# Sheet2.net
KiCad netlist of a schematic drawn in Altium Designer
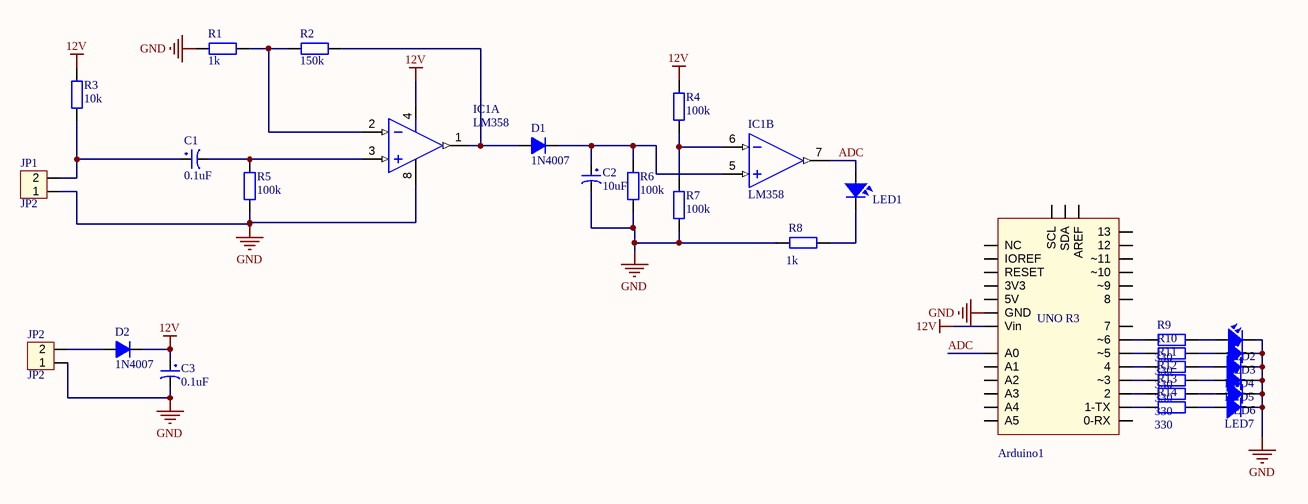
[diagram p0: Sheet2.SchDoc]

(export (version "E")
  (design (tool "Eeschema 10.0.6"))
  (components
    (comp (ref "Arduino1")
      (value "Arduino Uno R3")
      (footprint "Arduino UNO R3")
      (description "Arduino UNO R3")
      (libsource (lib "LIBRARY") (part "Arduino Uno R3"))
    )
    (comp (ref "C1")
      (value "0.1uF")
      (footprint "CP1/2")
      (description "Cap P  0,1uF < 22uF , 16 - 50V")
      (libsource (lib "") (part "CP1_1"))
    )
    (comp (ref "C2")
      (value "10uF")
      (footprint "CP1/2")
      (description "Cap P  0,1uF < 22uF , 16 - 50V")
      (libsource (lib "syhaunguyen") (part "CP1"))
    )
    (comp (ref "C3")
      (value "0.1uF")
      (footprint "CP1/2")
      (description "Cap P  0,1uF < 22uF , 16 - 50V")
      (libsource (lib "syhaunguyen") (part "CP1"))
    )
    (comp (ref "D1")
      (value "1N4007")
      (footprint "D1A")
      (description "Diode 1A")
      (libsource (lib "syhaunguyen") (part "D1A"))
    )
    (comp (ref "D2")
      (value "1N4007")
      (footprint "D1A")
      (description "Diode 1A")
      (libsource (lib "syhaunguyen") (part "D1A"))
    )
    (comp (ref "IC1")
      (value "LM358")
      (footprint "DIP8")
      (description "Low-Power Dual Operational Amplifier")
      (libsource (lib "LIBRARY") (part "LM358"))
    )
    (comp (ref "JP1")
      (value "JP2")
      (footprint "CON2")
      (description "Connector 2")
      (libsource (lib "syhaunguyen") (part "Con2"))
    )
    (comp (ref "JP2")
      (value "JP2")
      (footprint "CON2")
      (description "Connector 2")
      (libsource (lib "syhaunguyen") (part "Con2"))
    )
    (comp (ref "LED1")
      (value "LED")
      (footprint "LED-3")
      (description "LED Single colour Green and Red")
      (libsource (lib "syhaunguyen") (part "LED"))
    )
    (comp (ref "LED2")
      (value "LED")
      (footprint "LED-3")
      (description "LED Single colour Green and Red")
      (libsource (lib "syhaunguyen") (part "LED"))
    )
    (comp (ref "LED3")
      (value "LED")
      (footprint "LED-3")
      (description "LED Single colour Green and Red")
      (libsource (lib "syhaunguyen") (part "LED"))
    )
    (comp (ref "LED4")
      (value "LED")
      (footprint "LED-3")
      (description "LED Single colour Green and Red")
      (libsource (lib "syhaunguyen") (part "LED"))
    )
    (comp (ref "LED5")
      (value "LED")
      (footprint "LED-3")
      (description "LED Single colour Green and Red")
      (libsource (lib "syhaunguyen") (part "LED"))
    )
    (comp (ref "LED6")
      (value "LED")
      (footprint "LED-3")
      (description "LED Single colour Green and Red")
      (libsource (lib "syhaunguyen") (part "LED"))
    )
    (comp (ref "LED7")
      (value "LED")
      (footprint "LED-3")
      (description "LED Single colour Green and Red")
      (libsource (lib "syhaunguyen") (part "LED"))
    )
    (comp (ref "R1")
      (value "1k")
      (footprint "R1/4W")
      (description "Resistor 1/4W")
      (libsource (lib "syhaunguyen") (part "R1/4W"))
    )
    (comp (ref "R2")
      (value "150k")
      (footprint "R1/4W")
      (description "Resistor 1/4W")
      (libsource (lib "syhaunguyen") (part "R1/4W"))
    )
    (comp (ref "R3")
      (value "10k")
      (footprint "R1/4W")
      (description "Resistor 1/4W")
      (libsource (lib "syhaunguyen") (part "R1/4W"))
    )
    (comp (ref "R4")
      (value "100k")
      (footprint "R1/4W")
      (description "Resistor 1/4W")
      (libsource (lib "syhaunguyen") (part "R1/4W"))
    )
    (comp (ref "R5")
      (value "100k")
      (footprint "R1/4W")
      (description "Resistor 1/4W")
      (libsource (lib "syhaunguyen") (part "R1/4W"))
    )
    (comp (ref "R6")
      (value "100k")
      (footprint "R1/4W")
      (description "Resistor 1/4W")
      (libsource (lib "syhaunguyen") (part "R1/4W"))
    )
    (comp (ref "R7")
      (value "100k")
      (footprint "R1/4W")
      (description "Resistor 1/4W")
      (libsource (lib "syhaunguyen") (part "R1/4W"))
    )
    (comp (ref "R8")
      (value "1k")
      (footprint "R1/4W")
      (description "Resistor 1/4W")
      (libsource (lib "syhaunguyen") (part "R1/4W"))
    )
    (comp (ref "R9")
      (value "330")
      (footprint "R1/4W")
      (description "Resistor 1/4W")
      (libsource (lib "syhaunguyen") (part "R1/4W"))
    )
    (comp (ref "R10")
      (value "330")
      (footprint "R1/4W")
      (description "Resistor 1/4W")
      (libsource (lib "syhaunguyen") (part "R1/4W"))
    )
    (comp (ref "R11")
      (value "330")
      (footprint "R1/4W")
      (description "Resistor 1/4W")
      (libsource (lib "syhaunguyen") (part "R1/4W"))
    )
    (comp (ref "R12")
      (value "330")
      (footprint "R1/4W")
      (description "Resistor 1/4W")
      (libsource (lib "syhaunguyen") (part "R1/4W"))
    )
    (comp (ref "R13")
      (value "330")
      (footprint "R1/4W")
      (description "Resistor 1/4W")
      (libsource (lib "syhaunguyen") (part "R1/4W"))
    )
    (comp (ref "R14")
      (value "330")
      (footprint "R1/4W")
      (description "Resistor 1/4W")
      (libsource (lib "syhaunguyen") (part "R1/4W"))
    )
  )
  (nets
    (net (code "1") (name "/ADC") (class "Default")
      (node (ref "Arduino1") (pin "A0") (pinfunction "A0_A0") (pintype "passive"))
      (node (ref "IC1") (pin "7") (pinfunction "OUT_7") (pintype "output"))
      (node (ref "LED1") (pin "1") (pinfunction "1_1") (pintype "passive"))
    )
    (net (code "2") (name "12V") (class "Default")
      (node (ref "Arduino1") (pin "Vin") (pinfunction "Vin_Vin") (pintype "passive"))
      (node (ref "C3") (pin "1") (pinfunction "1_1") (pintype "passive"))
      (node (ref "D2") (pin "2") (pinfunction "K_2") (pintype "passive"))
      (node (ref "IC1") (pin "4") (pinfunction "-V_4") (pintype "passive"))
      (node (ref "R3") (pin "2") (pinfunction "2_2") (pintype "passive"))
      (node (ref "R4") (pin "2") (pinfunction "2_2") (pintype "passive"))
    )
    (net (code "3") (name "GND") (class "Default")
      (node (ref "Arduino1") (pin "GND") (pinfunction "GND_GND") (pintype "passive"))
      (node (ref "C2") (pin "2") (pinfunction "2_2") (pintype "passive"))
      (node (ref "C3") (pin "2") (pinfunction "2_2") (pintype "passive"))
      (node (ref "IC1") (pin "8") (pinfunction "+V_8") (pintype "passive"))
      (node (ref "JP1") (pin "1") (pinfunction "1_1") (pintype "passive"))
      (node (ref "JP2") (pin "1") (pinfunction "1_1") (pintype "passive"))
      (node (ref "LED2") (pin "2") (pinfunction "2_2") (pintype "passive"))
      (node (ref "LED3") (pin "2") (pinfunction "2_2") (pintype "passive"))
      (node (ref "LED4") (pin "2") (pinfunction "2_2") (pintype "passive"))
      (node (ref "LED5") (pin "2") (pinfunction "2_2") (pintype "passive"))
      (node (ref "LED6") (pin "2") (pinfunction "2_2") (pintype "passive"))
      (node (ref "LED7") (pin "2") (pinfunction "2_2") (pintype "passive"))
      (node (ref "R1") (pin "2") (pinfunction "2_2") (pintype "passive"))
      (node (ref "R5") (pin "1") (pinfunction "1_1") (pintype "passive"))
      (node (ref "R6") (pin "1") (pinfunction "1_1") (pintype "passive"))
      (node (ref "R7") (pin "1") (pinfunction "1_1") (pintype "passive"))
      (node (ref "R8") (pin "2") (pinfunction "2_2") (pintype "passive"))
    )
    (net (code "4") (name "Net-(Arduino1-Pad1-TX)") (class "Default")
      (node (ref "Arduino1") (pin "1-TX") (pinfunction "1-TX_1-TX") (pintype "passive"))
      (node (ref "R14") (pin "2") (pinfunction "2_2") (pintype "passive"))
    )
    (net (code "5") (name "Net-(Arduino1-Pad2)") (class "Default")
      (node (ref "Arduino1") (pin "2") (pinfunction "2_2") (pintype "passive"))
      (node (ref "R13") (pin "2") (pinfunction "2_2") (pintype "passive"))
    )
    (net (code "6") (name "Net-(Arduino1-Pad4)") (class "Default")
      (node (ref "Arduino1") (pin "4") (pinfunction "4_4") (pintype "passive"))
      (node (ref "R11") (pin "2") (pinfunction "2_2") (pintype "passive"))
    )
    (net (code "7") (name "Net-(Arduino1-Pad~3)") (class "Default")
      (node (ref "Arduino1") (pin "~3") (pinfunction "~3_~3") (pintype "passive"))
      (node (ref "R12") (pin "2") (pinfunction "2_2") (pintype "passive"))
    )
    (net (code "8") (name "Net-(Arduino1-Pad~5)") (class "Default")
      (node (ref "Arduino1") (pin "~5") (pinfunction "~5_~5") (pintype "passive"))
      (node (ref "R10") (pin "2") (pinfunction "2_2") (pintype "passive"))
    )
    (net (code "9") (name "Net-(Arduino1-Pad~6)") (class "Default")
      (node (ref "Arduino1") (pin "~6") (pinfunction "~6_~6") (pintype "passive"))
      (node (ref "R9") (pin "2") (pinfunction "2_2") (pintype "passive"))
    )
    (net (code "10") (name "Net-(C1-Pad1)") (class "Default")
      (node (ref "C1") (pin "1") (pinfunction "1_1") (pintype "passive"))
      (node (ref "JP1") (pin "2") (pinfunction "2_2") (pintype "passive"))
      (node (ref "R3") (pin "1") (pinfunction "1_1") (pintype "passive"))
    )
    (net (code "11") (name "Net-(D1-A)") (class "Default")
      (node (ref "D1") (pin "1") (pinfunction "A_1") (pintype "passive"))
      (node (ref "IC1") (pin "1") (pinfunction "OUT_1") (pintype "output"))
      (node (ref "R2") (pin "1") (pinfunction "1_1") (pintype "passive"))
    )
    (net (code "12") (name "Net-(D1-K)") (class "Default")
      (node (ref "C2") (pin "1") (pinfunction "1_1") (pintype "passive"))
      (node (ref "D1") (pin "2") (pinfunction "K_2") (pintype "passive"))
      (node (ref "IC1") (pin "5") (pinfunction "IN+_5") (pintype "input"))
      (node (ref "R6") (pin "2") (pinfunction "2_2") (pintype "passive"))
    )
    (net (code "13") (name "Net-(D2-A)") (class "Default")
      (node (ref "D2") (pin "1") (pinfunction "A_1") (pintype "passive"))
      (node (ref "JP2") (pin "2") (pinfunction "2_2") (pintype "passive"))
    )
    (net (code "14") (name "Net-(IC1A-IN+)") (class "Default")
      (node (ref "C1") (pin "2") (pinfunction "2_2") (pintype "passive"))
      (node (ref "IC1") (pin "3") (pinfunction "IN+_3") (pintype "input"))
      (node (ref "R5") (pin "2") (pinfunction "2_2") (pintype "passive"))
    )
    (net (code "15") (name "Net-(IC1A-IN-)") (class "Default")
      (node (ref "IC1") (pin "2") (pinfunction "IN-_2") (pintype "input"))
      (node (ref "R1") (pin "1") (pinfunction "1_1") (pintype "passive"))
      (node (ref "R2") (pin "2") (pinfunction "2_2") (pintype "passive"))
    )
    (net (code "16") (name "Net-(IC1B-IN-)") (class "Default")
      (node (ref "IC1") (pin "6") (pinfunction "IN-_6") (pintype "input"))
      (node (ref "R4") (pin "1") (pinfunction "1_1") (pintype "passive"))
      (node (ref "R7") (pin "2") (pinfunction "2_2") (pintype "passive"))
    )
    (net (code "17") (name "Net-(LED1-Pad2)") (class "Default")
      (node (ref "LED1") (pin "2") (pinfunction "2_2") (pintype "passive"))
      (node (ref "R8") (pin "1") (pinfunction "1_1") (pintype "passive"))
    )
    (net (code "18") (name "Net-(LED2-Pad1)") (class "Default")
      (node (ref "LED2") (pin "1") (pinfunction "1_1") (pintype "passive"))
      (node (ref "R9") (pin "1") (pinfunction "1_1") (pintype "passive"))
    )
    (net (code "19") (name "Net-(LED3-Pad1)") (class "Default")
      (node (ref "LED3") (pin "1") (pinfunction "1_1") (pintype "passive"))
      (node (ref "R10") (pin "1") (pinfunction "1_1") (pintype "passive"))
    )
    (net (code "20") (name "Net-(LED4-Pad1)") (class "Default")
      (node (ref "LED4") (pin "1") (pinfunction "1_1") (pintype "passive"))
      (node (ref "R11") (pin "1") (pinfunction "1_1") (pintype "passive"))
    )
    (net (code "21") (name "Net-(LED5-Pad1)") (class "Default")
      (node (ref "LED5") (pin "1") (pinfunction "1_1") (pintype "passive"))
      (node (ref "R12") (pin "1") (pinfunction "1_1") (pintype "passive"))
    )
    (net (code "22") (name "Net-(LED6-Pad1)") (class "Default")
      (node (ref "LED6") (pin "1") (pinfunction "1_1") (pintype "passive"))
      (node (ref "R13") (pin "1") (pinfunction "1_1") (pintype "passive"))
    )
    (net (code "23") (name "Net-(LED7-Pad1)") (class "Default")
      (node (ref "LED7") (pin "1") (pinfunction "1_1") (pintype "passive"))
      (node (ref "R14") (pin "1") (pinfunction "1_1") (pintype "passive"))
    )
    (net (code "24") (name "unconnected-(Arduino1-Pad0-RX)") (class "Default")
      (node (ref "Arduino1") (pin "0-RX") (pinfunction "0-RX_0-RX") (pintype "passive"))
    )
    (net (code "25") (name "unconnected-(Arduino1-Pad3V3)") (class "Default")
      (node (ref "Arduino1") (pin "3V3") (pinfunction "3V3_3V3") (pintype "passive"))
    )
    (net (code "26") (name "unconnected-(Arduino1-Pad5V)") (class "Default")
      (node (ref "Arduino1") (pin "5V") (pinfunction "5V_5V") (pintype "passive"))
    )
    (net (code "27") (name "unconnected-(Arduino1-Pad7)") (class "Default")
      (node (ref "Arduino1") (pin "7") (pinfunction "7_7") (pintype "passive"))
    )
    (net (code "28") (name "unconnected-(Arduino1-Pad8)") (class "Default")
      (node (ref "Arduino1") (pin "8") (pinfunction "8_8") (pintype "passive"))
    )
    (net (code "29") (name "unconnected-(Arduino1-Pad12)") (class "Default")
      (node (ref "Arduino1") (pin "12") (pinfunction "12_12") (pintype "passive"))
    )
    (net (code "30") (name "unconnected-(Arduino1-Pad13)") (class "Default")
      (node (ref "Arduino1") (pin "13") (pinfunction "13_13") (pintype "passive"))
    )
    (net (code "31") (name "unconnected-(Arduino1-PadA1)") (class "Default")
      (node (ref "Arduino1") (pin "A1") (pinfunction "A1_A1") (pintype "passive"))
    )
    (net (code "32") (name "unconnected-(Arduino1-PadA2)") (class "Default")
      (node (ref "Arduino1") (pin "A2") (pinfunction "A2_A2") (pintype "passive"))
    )
    (net (code "33") (name "unconnected-(Arduino1-PadA3)") (class "Default")
      (node (ref "Arduino1") (pin "A3") (pinfunction "A3_A3") (pintype "passive"))
    )
    (net (code "34") (name "unconnected-(Arduino1-PadA4)") (class "Default")
      (node (ref "Arduino1") (pin "A4") (pinfunction "A4_A4") (pintype "passive"))
    )
    (net (code "35") (name "unconnected-(Arduino1-PadA5)") (class "Default")
      (node (ref "Arduino1") (pin "A5") (pinfunction "A5_A5") (pintype "passive"))
    )
    (net (code "36") (name "unconnected-(Arduino1-PadAREF)") (class "Default")
      (node (ref "Arduino1") (pin "AREF") (pinfunction "AREF_AREF") (pintype "passive"))
    )
    (net (code "37") (name "unconnected-(Arduino1-PadIOREF)") (class "Default")
      (node (ref "Arduino1") (pin "IOREF") (pinfunction "IOREF_IOREF") (pintype "passive"))
    )
    (net (code "38") (name "unconnected-(Arduino1-PadNC)") (class "Default")
      (node (ref "Arduino1") (pin "NC") (pinfunction "NC_NC") (pintype "passive"))
    )
    (net (code "39") (name "unconnected-(Arduino1-PadRESET)") (class "Default")
      (node (ref "Arduino1") (pin "RESET") (pinfunction "RESET_RESET") (pintype "passive"))
    )
    (net (code "40") (name "unconnected-(Arduino1-PadSCL)") (class "Default")
      (node (ref "Arduino1") (pin "SCL") (pinfunction "SCL_SCL") (pintype "passive"))
    )
    (net (code "41") (name "unconnected-(Arduino1-PadSDA)") (class "Default")
      (node (ref "Arduino1") (pin "SDA") (pinfunction "SDA_SDA") (pintype "passive"))
    )
    (net (code "42") (name "unconnected-(Arduino1-Pad~9)") (class "Default")
      (node (ref "Arduino1") (pin "~9") (pinfunction "~9_~9") (pintype "passive"))
    )
    (net (code "43") (name "unconnected-(Arduino1-Pad~10)") (class "Default")
      (node (ref "Arduino1") (pin "~10") (pinfunction "~10_~10") (pintype "passive"))
    )
    (net (code "44") (name "unconnected-(Arduino1-Pad~11)") (class "Default")
      (node (ref "Arduino1") (pin "~11") (pinfunction "~11_~11") (pintype "passive"))
    )
  )
)
